# Power.net
KiCad netlist of a schematic drawn in Altium Designer
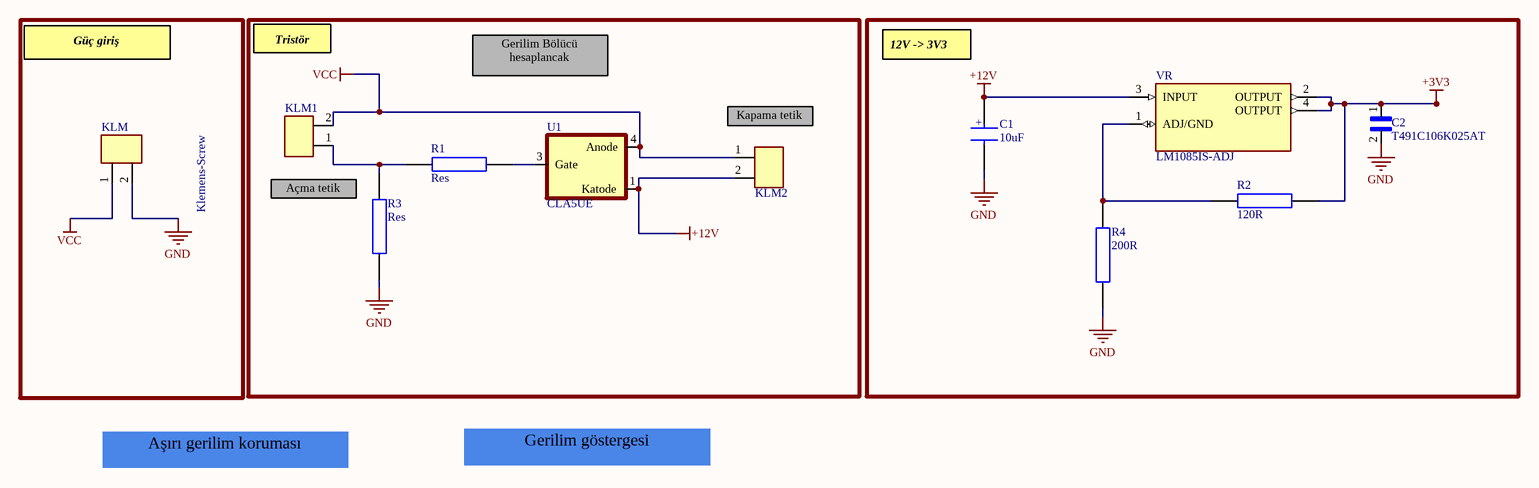
[diagram p0: Power.SchDoc]

(export (version "E")
  (design (tool "Eeschema 10.0.6"))
  (components
    (comp (ref "C1")
      (value "10uF")
      (footprint "CAP_805")
      (description "0805 smd")
      (libsource (lib "Udemy_Schlib1") (part "CAP 1uF"))
    )
    (comp (ref "C2")
      (value "T491C106K025AT")
      (footprint "CAPPC6032X280N")
      (description "10 ÂµF Molded Tantalum Capacitors 25 V 2312 (6032 Metric) 1.5Ohm")
      (fields (field (name "MF") "KEMET"))
      (libsource (lib "T491C106K025AT") (part "T491C106K025AT"))
    )
    (comp (ref "KLM")
      (value "Klemens-Screw")
      (footprint "Klemens-ScrewMount")
      (libsource (lib "Schlib") (part "Klemens-Screw"))
    )
    (comp (ref "KLM1")
      (value "Klemens-Screw")
      (footprint "Klemens-ScrewMount")
      (libsource (lib "") (part "Klemens-Screw_1"))
    )
    (comp (ref "KLM2")
      (value "Klemens-Screw")
      (footprint "Klemens-ScrewMount")
      (libsource (lib "") (part "Klemens-Screw_2"))
    )
    (comp (ref "R1")
      (value "Res")
      (footprint "RES_1206")
      (libsource (lib "Udemy_Schlib1") (part "RES 1K 1206"))
    )
    (comp (ref "R2")
      (value "120R")
      (footprint "RES_1206")
      (libsource (lib "Udemy_Schlib1") (part "RES 1K 1206"))
    )
    (comp (ref "R3")
      (value "Res")
      (footprint "RES_1206")
      (libsource (lib "Udemy_Schlib1") (part "RES 1K 1206"))
    )
    (comp (ref "R4")
      (value "200R")
      (footprint "RES_1206")
      (libsource (lib "Udemy_Schlib1") (part "RES 1K 1206"))
    )
    (comp (ref "U1")
      (value "CLA5UE")
      (footprint "DPAK229P990X239-4N")
      (libsource (lib "Schlib") (part "CLA5UE"))
    )
    (comp (ref "VR")
      (value "LM1085IS-ADJ")
      (footprint "TO254P1524X483-4N")
      (description "3-A, 29-V, linear voltage regulator 3-DDPAK/TO-263")
      (fields (field (name "MF") "Texas Instruments"))
      (libsource (lib "Schlib") (part "LM1085IS-ADJ"))
    )
  )
  (nets
    (net (code "1") (name "+3V3") (class "Default")
      (node (ref "C2") (pin "1") (pinfunction "1_1") (pintype "passive"))
      (node (ref "R2") (pin "1") (pintype "passive"))
      (node (ref "VR") (pin "2") (pinfunction "OUTPUT_2") (pintype "output"))
      (node (ref "VR") (pin "4") (pinfunction "OUTPUT_4") (pintype "output"))
    )
    (net (code "2") (name "+12V") (class "Default")
      (node (ref "C1") (pin "1") (pinfunction "1_1") (pintype "passive"))
      (node (ref "KLM2") (pin "2") (pintype "passive"))
      (node (ref "U1") (pin "1") (pinfunction "Katode_1") (pintype "passive"))
      (node (ref "VR") (pin "3") (pinfunction "INPUT_3") (pintype "input"))
    )
    (net (code "3") (name "GND") (class "Default")
      (node (ref "C1") (pin "2") (pinfunction "2_2") (pintype "passive"))
      (node (ref "C2") (pin "2") (pinfunction "2_2") (pintype "passive"))
      (node (ref "KLM") (pin "2") (pintype "passive"))
      (node (ref "R3") (pin "1") (pintype "passive"))
      (node (ref "R4") (pin "1") (pintype "passive"))
    )
    (net (code "4") (name "Net-(KLM1-Pad1)") (class "Default")
      (node (ref "KLM1") (pin "1") (pintype "passive"))
      (node (ref "R1") (pin "2") (pintype "passive"))
      (node (ref "R3") (pin "2") (pintype "passive"))
    )
    (net (code "5") (name "Net-(U1-Gate)") (class "Default")
      (node (ref "R1") (pin "1") (pintype "passive"))
      (node (ref "U1") (pin "3") (pinfunction "Gate_3") (pintype "passive"))
    )
    (net (code "6") (name "Net-(VR-ADJ{slash}GND)") (class "Default")
      (node (ref "R2") (pin "2") (pintype "passive"))
      (node (ref "R4") (pin "2") (pintype "passive"))
      (node (ref "VR") (pin "1") (pinfunction "ADJ/GND_1") (pintype "bidirectional"))
    )
    (net (code "7") (name "VCC") (class "Default")
      (node (ref "KLM") (pin "1") (pintype "passive"))
      (node (ref "KLM1") (pin "2") (pintype "passive"))
      (node (ref "KLM2") (pin "1") (pintype "passive"))
      (node (ref "U1") (pin "4") (pinfunction "Anode_4") (pintype "passive"))
    )
  )
)
